# HBridge_Top_Level.net
KiCad netlist of a schematic drawn in Altium Designer
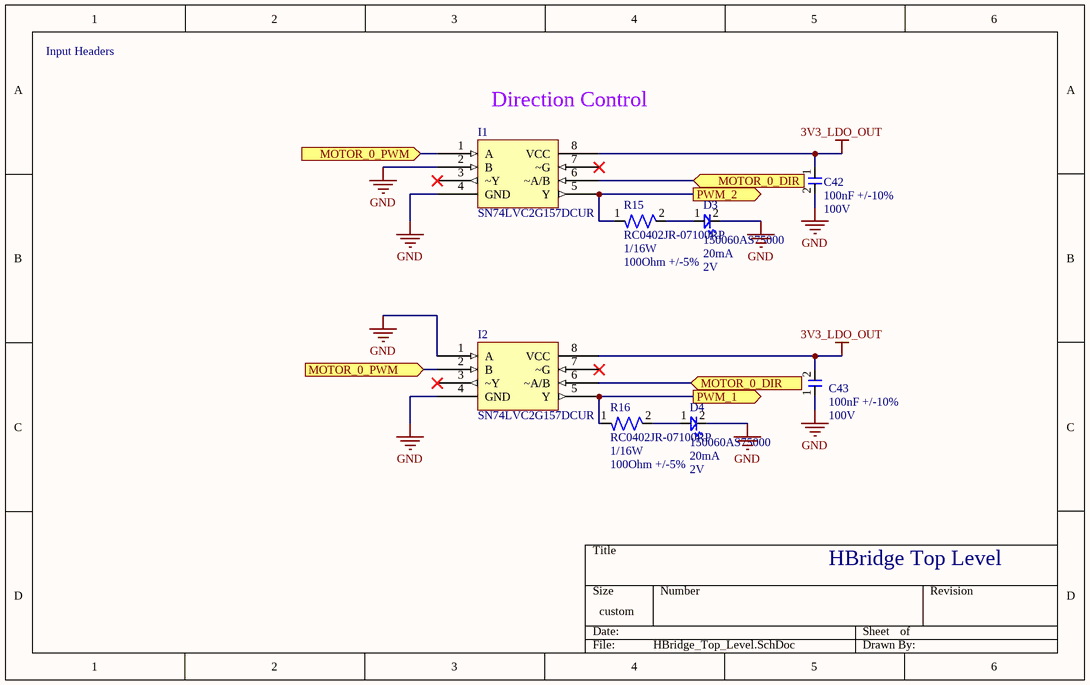
[diagram p0: HBridge_Top_Level.SchDoc]

(export (version "E")
  (design (tool "Eeschema 10.0.6"))
  (components
    (comp (ref "C42")
      (value "CC0603KRX7R0BB104")
      (footprint "CAP-0603")
      (description "CAP CER 0.1UF 100V X7R 0603")
      (fields
        (field (name "MANUFACTURER") "YAGEO")
        (field (name "CAPACITANCE") "100nF +/-10%")
        (field (name "VOLTAGE RATING") "100V")
      )
      (libsource (lib "MasterLib") (part "CAP-100N-0001"))
    )
    (comp (ref "C43")
      (value "CC0603KRX7R0BB104")
      (footprint "CAP-0603")
      (description "CAP CER 0.1UF 100V X7R 0603")
      (fields
        (field (name "MANUFACTURER") "YAGEO")
        (field (name "CAPACITANCE") "100nF +/-10%")
        (field (name "VOLTAGE RATING") "100V")
      )
      (libsource (lib "MasterLib") (part "CAP-100N-0001"))
    )
    (comp (ref "D3")
      (value "150060AS75000")
      (footprint "LED-0603")
      (description "CAP CER 0.1UF 100V X7R 0603")
      (fields
        (field (name "MANUFACTURER") "Wurth Electronik")
        (field (name "CURRENT RATING") "20mA")
        (field (name "VF") "2V")
      )
      (libsource (lib "MasterLib") (part "LED_Amber_0001"))
    )
    (comp (ref "D4")
      (value "150060AS75000")
      (footprint "LED-0603")
      (description "CAP CER 0.1UF 100V X7R 0603")
      (fields
        (field (name "MANUFACTURER") "Wurth Electronik")
        (field (name "CURRENT RATING") "20mA")
        (field (name "VF") "2V")
      )
      (libsource (lib "MasterLib") (part "LED_Amber_0001"))
    )
    (comp (ref "I1")
      (value "SN74LVC2G157DCUR")
      (footprint "IC-MUX-8VSSOP")
      (libsource (lib "MasterLib") (part "IC-MUX-0001"))
    )
    (comp (ref "I2")
      (value "SN74LVC2G157DCUR")
      (footprint "IC-MUX-8VSSOP")
      (description "Multiplexer 1 x 2:1 8-VSSOP")
      (libsource (lib "MasterLib") (part "IC-MUX-0001"))
    )
    (comp (ref "R15")
      (value "RC0402JR-07100RP")
      (footprint "RES-0402")
      (description "RES SMD 100 OHM 5% 1/16W 0402")
      (fields
        (field (name "MANUFACTURER") "YAGEO")
        (field (name "POWER RATING") "1/16W")
        (field (name "RESISTANCE") "100Ohm +/-5%")
      )
      (libsource (lib "MasterLib") (part "RES-100-0001"))
    )
    (comp (ref "R16")
      (value "RC0402JR-07100RP")
      (footprint "RES-0402")
      (description "RES SMD 100 OHM 5% 1/16W 0402")
      (fields
        (field (name "MANUFACTURER") "YAGEO")
        (field (name "POWER RATING") "1/16W")
        (field (name "RESISTANCE") "100Ohm +/-5%")
      )
      (libsource (lib "MasterLib") (part "RES-100-0001"))
    )
  )
  (nets
    (net (code "1") (name "/MOTOR_0_DIR") (class "Default")
      (node (ref "I1") (pin "6") (pinfunction "~A/B_6") (pintype "input"))
      (node (ref "I2") (pin "6") (pinfunction "~A/B_6") (pintype "input"))
    )
    (net (code "2") (name "/MOTOR_0_PWM") (class "Default")
      (node (ref "I1") (pin "1") (pinfunction "A_1") (pintype "input"))
      (node (ref "I2") (pin "2") (pinfunction "B_2") (pintype "input"))
    )
    (net (code "3") (name "/PWM_1") (class "Default")
      (node (ref "I2") (pin "5") (pinfunction "Y_5") (pintype "output"))
      (node (ref "R16") (pin "1") (pinfunction "1_1") (pintype "passive"))
    )
    (net (code "4") (name "/PWM_2") (class "Default")
      (node (ref "I1") (pin "5") (pinfunction "Y_5") (pintype "output"))
      (node (ref "R15") (pin "1") (pinfunction "1_1") (pintype "passive"))
    )
    (net (code "5") (name "3V3_LDO_OUT") (class "Default")
      (node (ref "C42") (pin "1") (pinfunction "1_1") (pintype "passive"))
      (node (ref "C43") (pin "2") (pinfunction "2_2") (pintype "passive"))
      (node (ref "I1") (pin "8") (pinfunction "VCC_8") (pintype "power_in"))
      (node (ref "I2") (pin "8") (pinfunction "VCC_8") (pintype "power_in"))
    )
    (net (code "6") (name "GND") (class "Default")
      (node (ref "C42") (pin "2") (pinfunction "2_2") (pintype "passive"))
      (node (ref "C43") (pin "1") (pinfunction "1_1") (pintype "passive"))
      (node (ref "D3") (pin "2") (pinfunction "2_2") (pintype "passive"))
      (node (ref "D4") (pin "2") (pinfunction "2_2") (pintype "passive"))
      (node (ref "I1") (pin "2") (pinfunction "B_2") (pintype "input"))
      (node (ref "I1") (pin "4") (pinfunction "GND_4") (pintype "power_in"))
      (node (ref "I2") (pin "1") (pinfunction "A_1") (pintype "input"))
      (node (ref "I2") (pin "4") (pinfunction "GND_4") (pintype "power_in"))
    )
    (net (code "7") (name "Net-(D3-Pad1)") (class "Default")
      (node (ref "D3") (pin "1") (pinfunction "1_1") (pintype "passive"))
      (node (ref "R15") (pin "2") (pinfunction "2_2") (pintype "passive"))
    )
    (net (code "8") (name "Net-(D4-Pad1)") (class "Default")
      (node (ref "D4") (pin "1") (pinfunction "1_1") (pintype "passive"))
      (node (ref "R16") (pin "2") (pinfunction "2_2") (pintype "passive"))
    )
    (net (code "9") (name "unconnected-(I1-~G-Pad7)") (class "Default")
      (node (ref "I1") (pin "7") (pinfunction "~G_7") (pintype "input+no_connect"))
    )
    (net (code "10") (name "unconnected-(I1-~Y-Pad3)") (class "Default")
      (node (ref "I1") (pin "3") (pinfunction "~Y_3") (pintype "output+no_connect"))
    )
    (net (code "11") (name "unconnected-(I2-~G-Pad7)") (class "Default")
      (node (ref "I2") (pin "7") (pinfunction "~G_7") (pintype "input+no_connect"))
    )
    (net (code "12") (name "unconnected-(I2-~Y-Pad3)") (class "Default")
      (node (ref "I2") (pin "3") (pinfunction "~Y_3") (pintype "output+no_connect"))
    )
  )
)
